# ProPrj_Flipper_Wifi_and_433MHz_shield_20.net
KiCad netlist of a schematic drawn in EasyEDA Pro
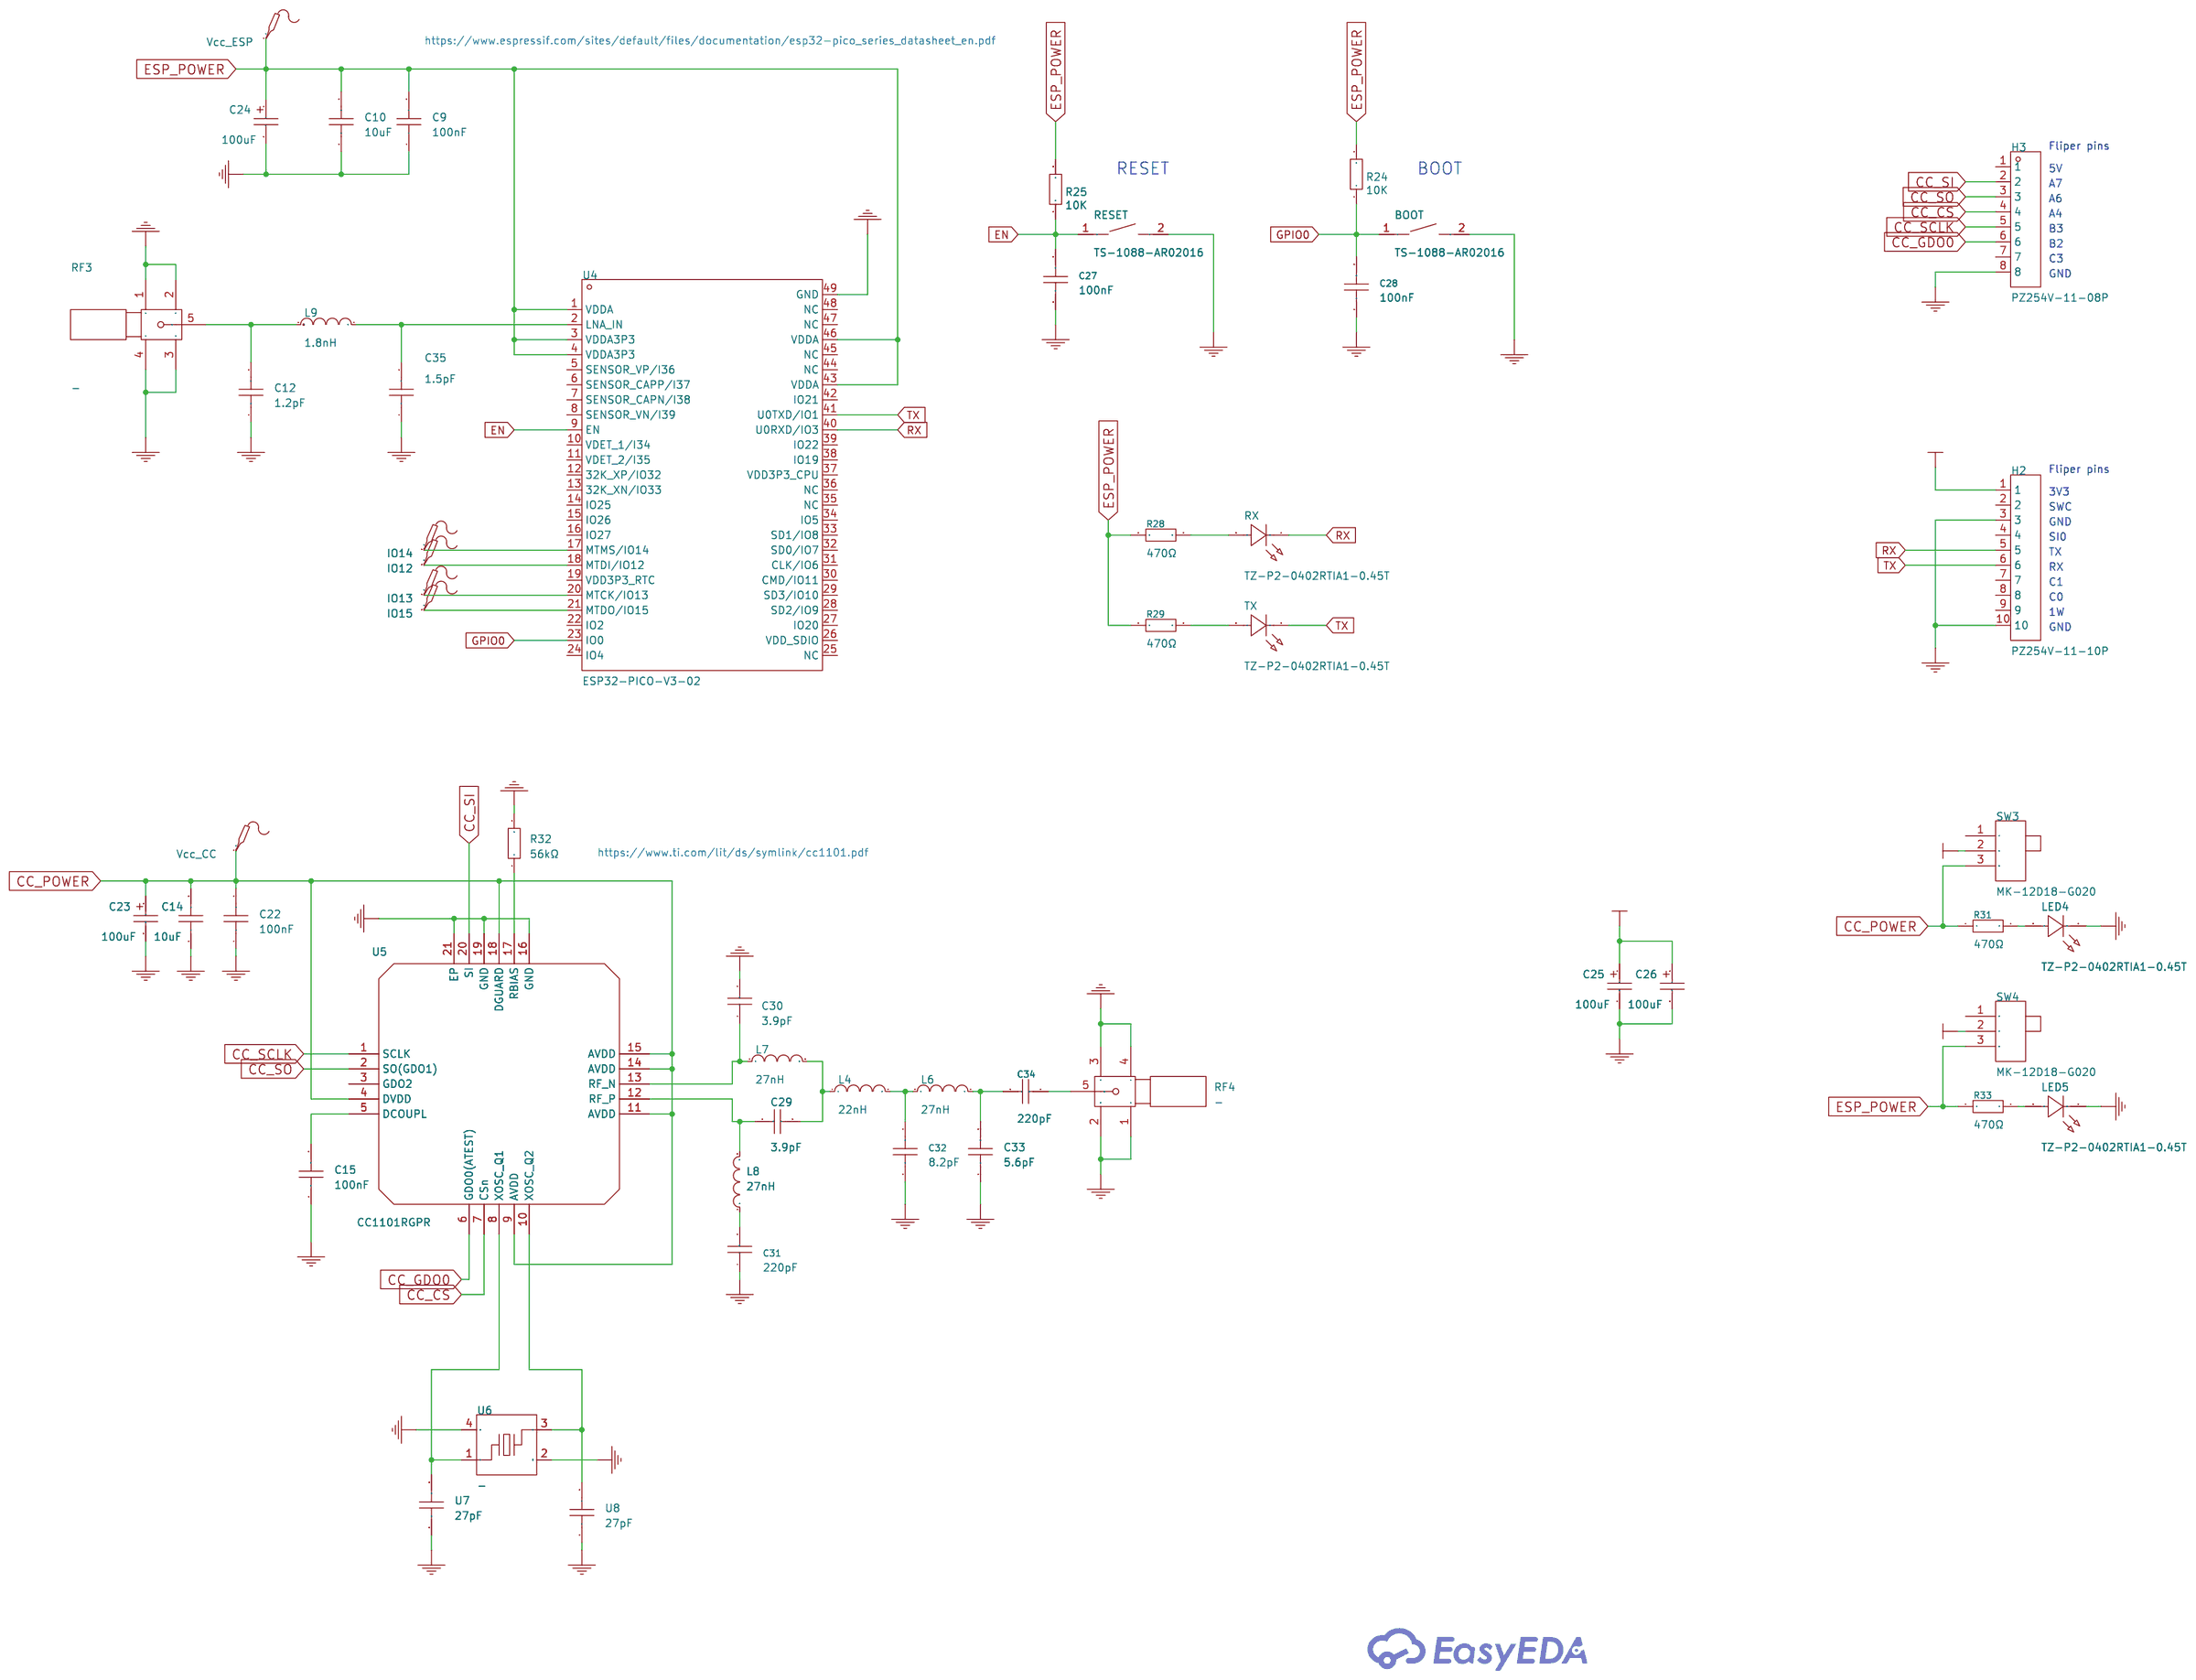
[diagram p0: schematic sheet]

(export (version "E")
  (design (tool "Eeschema 10.0.6"))
  (components
    (comp (ref "BOOT")
      (value "TS-1088-AR02016")
      (footprint "easyedapro:SW-SMD_L3.9-W3.0-P4.45")
      (fields (field (name "Manufacturer") "XUNPU(讯普)"))
      (libsource (lib "easyedapro") (part "TS-1088-AR02016"))
    )
    (comp (ref "C9")
      (value "100nF")
      (footprint "easyedapro:C0603")
      (description "Capacitance:100nF Tolerance:±10% Tolerance:±10% Voltage Rating:50V Temperature Coefficient:X7R")
      (fields
        (field (name "Manufacturer Part") "CC0603KRX7R9BB104")
        (field (name "Manufacturer") "YAGEO(国巨)")
      )
      (libsource (lib "easyedapro") (part "CC0603KRX7R9BB104"))
    )
    (comp (ref "C10")
      (value "10uF")
      (footprint "easyedapro:C0603")
      (fields
        (field (name "Manufacturer Part") "CL10A106MP8NNNC")
        (field (name "Manufacturer") "SAMSUNG(三星)")
      )
      (libsource (lib "easyedapro") (part "CL10A106MP8NNNC"))
    )
    (comp (ref "C12")
      (value "1.2pF")
      (footprint "easyedapro:C0201")
      (fields
        (field (name "Manufacturer Part") "GRM0335C1H1R2BA01D")
        (field (name "Manufacturer") "muRata(村田)")
      )
      (libsource (lib "easyedapro") (part "GRM0335C1H1R2BA01D"))
    )
    (comp (ref "C14")
      (value "10uF")
      (footprint "easyedapro:C0603")
      (fields
        (field (name "Manufacturer Part") "CL10A106MP8NNNC")
        (field (name "Manufacturer") "SAMSUNG(三星)")
      )
      (libsource (lib "easyedapro") (part "CL10A106MP8NNNC"))
    )
    (comp (ref "C15")
      (value "100nF")
      (footprint "easyedapro:C0603")
      (description "Capacitance:100nF Tolerance:±10% Tolerance:±10% Voltage Rating:50V Temperature Coefficient:X7R")
      (fields
        (field (name "Manufacturer Part") "CC0603KRX7R9BB104")
        (field (name "Manufacturer") "YAGEO(国巨)")
      )
      (libsource (lib "easyedapro") (part "CC0603KRX7R9BB104"))
    )
    (comp (ref "C22")
      (value "100nF")
      (footprint "easyedapro:C0603")
      (description "Capacitance:100nF Tolerance:±10% Tolerance:±10% Voltage Rating:50V Temperature Coefficient:X7R")
      (fields
        (field (name "Manufacturer Part") "CC0603KRX7R9BB104")
        (field (name "Manufacturer") "YAGEO(国巨)")
      )
      (libsource (lib "easyedapro") (part "CC0603KRX7R9BB104"))
    )
    (comp (ref "C23")
      (value "100uF")
      (footprint "easyedapro:CASE-B_3528")
      (fields (field (name "Manufacturer Part") "TAJB107K006RNJ") (field (name "Manufacturer") "Kyocera AVX"))
      (libsource (lib "easyedapro") (part "TAJB107K006RNJ"))
    )
    (comp (ref "C24")
      (value "100uF")
      (footprint "easyedapro:CASE-B_3528")
      (fields (field (name "Manufacturer Part") "TAJB107K006RNJ") (field (name "Manufacturer") "Kyocera AVX"))
      (libsource (lib "easyedapro") (part "TAJB107K006RNJ"))
    )
    (comp (ref "C25")
      (value "100uF")
      (footprint "easyedapro:CASE-B_3528")
      (fields (field (name "Manufacturer Part") "TAJB107K006RNJ") (field (name "Manufacturer") "Kyocera AVX"))
      (libsource (lib "easyedapro") (part "TAJB107K006RNJ"))
    )
    (comp (ref "C26")
      (value "100uF")
      (footprint "easyedapro:CASE-B_3528")
      (fields (field (name "Manufacturer Part") "TAJB107K006RNJ") (field (name "Manufacturer") "Kyocera AVX"))
      (libsource (lib "easyedapro") (part "TAJB107K006RNJ"))
    )
    (comp (ref "C27")
      (value "100nF")
      (footprint "easyedapro:C0402")
      (fields
        (field (name "Manufacturer Part") "CC0402KRX7R7BB104")
        (field (name "Manufacturer") "YAGEO(国巨)")
      )
      (libsource (lib "easyedapro") (part "CC0402KRX7R7BB104"))
    )
    (comp (ref "C28")
      (value "100nF")
      (footprint "easyedapro:C0402")
      (fields
        (field (name "Manufacturer Part") "CC0402KRX7R7BB104")
        (field (name "Manufacturer") "YAGEO(国巨)")
      )
      (libsource (lib "easyedapro") (part "CC0402KRX7R7BB104"))
    )
    (comp (ref "C29")
      (value "3.9pF")
      (footprint "easyedapro:C0402")
      (fields (field (name "Manufacturer Part") "0402CG3R9C500NT") (field (name "Manufacturer") "FH(风华)"))
      (libsource (lib "easyedapro") (part "0402CG3R9C500NT"))
    )
    (comp (ref "C30")
      (value "3.9pF")
      (footprint "easyedapro:C0402")
      (fields (field (name "Manufacturer Part") "0402CG3R9C500NT") (field (name "Manufacturer") "FH(风华)"))
      (libsource (lib "easyedapro") (part "0402CG3R9C500NT"))
    )
    (comp (ref "C31")
      (value "220pF")
      (footprint "easyedapro:C0402")
      (description "Capacitance:220pF Tolerance:±5% Tolerance:±5% Voltage Rating:50V Temperature Coefficient:NP0")
      (fields
        (field (name "Manufacturer Part") "CC0402JRNPO9BN221")
        (field (name "Manufacturer") "YAGEO(国巨)")
      )
      (libsource (lib "easyedapro") (part "CC0402JRNPO9BN221"))
    )
    (comp (ref "C32")
      (value "8.2pF")
      (footprint "easyedapro:C0402")
      (fields
        (field (name "Manufacturer Part") "CC0402BRNPO9BN8R2")
        (field (name "Manufacturer") "YAGEO(国巨)")
      )
      (libsource (lib "easyedapro") (part "CC0402BRNPO9BN8R2"))
    )
    (comp (ref "C33")
      (value "5.6pF")
      (footprint "easyedapro:C0402")
      (fields
        (field (name "Manufacturer Part") "CC0402BRNPO9BN5R6")
        (field (name "Manufacturer") "YAGEO(国巨)")
      )
      (libsource (lib "easyedapro") (part "CC0402BRNPO9BN5R6"))
    )
    (comp (ref "C34")
      (value "220pF")
      (footprint "easyedapro:C0402")
      (description "Capacitance:220pF Tolerance:±5% Tolerance:±5% Voltage Rating:50V Temperature Coefficient:NP0")
      (fields
        (field (name "Manufacturer Part") "CC0402JRNPO9BN221")
        (field (name "Manufacturer") "YAGEO(国巨)")
      )
      (libsource (lib "easyedapro") (part "CC0402JRNPO9BN221"))
    )
    (comp (ref "C35")
      (value "1.5pF")
      (footprint "easyedapro:C0201")
      (fields
        (field (name "Manufacturer Part") "GRM0335C1H1R5BA01D")
        (field (name "Manufacturer") "muRata(村田)")
      )
      (libsource (lib "easyedapro") (part "GRM0335C1H1R5BA01D"))
    )
    (comp (ref "H2")
      (value "PZ254V-11-10P")
      (footprint "easyedapro:HDR-TH_10P-P2.54-V-M")
      (fields (field (name "Manufacturer") "XFCN(兴飞)"))
      (libsource (lib "easyedapro") (part "PZ254V-11-10P"))
    )
    (comp (ref "H3")
      (value "PZ254V-11-08P")
      (footprint "easyedapro:HDR-TH_8P-P2.54-V-M")
      (fields (field (name "Manufacturer") "XFCN(兴飞)"))
      (libsource (lib "easyedapro") (part "PZ254V-11-08P"))
    )
    (comp (ref "IO12")
      (value "~")
      (footprint "easyedapro:Test-Point-0.5mm")
      (description "Test Point 测试点")
      (libsource (lib "easyedapro") (part "Test-Point"))
    )
    (comp (ref "IO13")
      (value "~")
      (footprint "easyedapro:Test-Point-0.5mm")
      (description "Test Point 测试点")
      (libsource (lib "easyedapro") (part "Test-Point"))
    )
    (comp (ref "IO14")
      (value "~")
      (footprint "easyedapro:Test-Point-0.5mm")
      (description "Test Point 测试点")
      (libsource (lib "easyedapro") (part "Test-Point"))
    )
    (comp (ref "IO15")
      (value "~")
      (footprint "easyedapro:Test-Point-0.5mm")
      (description "Test Point 测试点")
      (libsource (lib "easyedapro") (part "Test-Point"))
    )
    (comp (ref "L4")
      (value "22nH")
      (footprint "easyedapro:L0402")
      (fields (field (name "Manufacturer Part") "LQG15HS22NJ02D") (field (name "Manufacturer") "muRata(村田)"))
      (libsource (lib "easyedapro") (part "LQG15HS22NJ02D"))
    )
    (comp (ref "L6")
      (value "27nH")
      (footprint "easyedapro:L0402-RD")
      (fields (field (name "Manufacturer Part") "LQG15HS27NJ02D") (field (name "Manufacturer") "muRata(村田)"))
      (libsource (lib "easyedapro") (part "LQG15HS27NJ02D"))
    )
    (comp (ref "L7")
      (value "27nH")
      (footprint "easyedapro:L0402-RD")
      (fields (field (name "Manufacturer Part") "LQG15HS27NJ02D") (field (name "Manufacturer") "muRata(村田)"))
      (libsource (lib "easyedapro") (part "LQG15HS27NJ02D"))
    )
    (comp (ref "L8")
      (value "27nH")
      (footprint "easyedapro:L0402-RD")
      (fields (field (name "Manufacturer Part") "LQG15HS27NJ02D") (field (name "Manufacturer") "muRata(村田)"))
      (libsource (lib "easyedapro") (part "LQG15HS27NJ02D"))
    )
    (comp (ref "L9")
      (value "1.8nH")
      (footprint "easyedapro:L0201-RD")
      (fields (field (name "Manufacturer Part") "LQP03TN1N8B02D") (field (name "Manufacturer") "muRata(村田)"))
      (libsource (lib "easyedapro") (part "LQP03TN1N8B02D"))
    )
    (comp (ref "LED4")
      (value "TZ-P2-0402RTIA1-0.45T")
      (footprint "easyedapro:LED0402-RD_RED")
      (fields (field (name "Manufacturer") "TUOZHAN(拓展光电)"))
      (libsource (lib "easyedapro") (part "TZ-P2-0402RTIA1-0.45T"))
    )
    (comp (ref "LED5")
      (value "TZ-P2-0402RTIA1-0.45T")
      (footprint "easyedapro:LED0402-RD_RED")
      (fields (field (name "Manufacturer") "TUOZHAN(拓展光电)"))
      (libsource (lib "easyedapro") (part "TZ-P2-0402RTIA1-0.45T"))
    )
    (comp (ref "R24")
      (value "10K")
      (footprint "easyedapro:R0603")
      (fields (field (name "Manufacturer Part") "RC0603DR-0710KL") (field (name "Manufacturer") "YAGEO(国巨)"))
      (libsource (lib "easyedapro") (part "10K"))
    )
    (comp (ref "R25")
      (value "10K")
      (footprint "easyedapro:R0603")
      (fields (field (name "Manufacturer Part") "RC0603DR-0710KL") (field (name "Manufacturer") "YAGEO(国巨)"))
      (libsource (lib "easyedapro") (part "10K"))
    )
    (comp (ref "R28")
      (value "470Ω")
      (footprint "easyedapro:R0402")
      (fields
        (field (name "Manufacturer Part") "0402WGF4700TCE")
        (field (name "Manufacturer") "UNI-ROYAL(厚声)")
      )
      (libsource (lib "easyedapro") (part "0402WGF4700TCE"))
    )
    (comp (ref "R29")
      (value "470Ω")
      (footprint "easyedapro:R0402")
      (fields
        (field (name "Manufacturer Part") "0402WGF4700TCE")
        (field (name "Manufacturer") "UNI-ROYAL(厚声)")
      )
      (libsource (lib "easyedapro") (part "0402WGF4700TCE"))
    )
    (comp (ref "R31")
      (value "470Ω")
      (footprint "easyedapro:R0402")
      (fields
        (field (name "Manufacturer Part") "0402WGF4700TCE")
        (field (name "Manufacturer") "UNI-ROYAL(厚声)")
      )
      (libsource (lib "easyedapro") (part "0402WGF4700TCE"))
    )
    (comp (ref "R32")
      (value "56kΩ")
      (footprint "easyedapro:R0402")
      (fields
        (field (name "Manufacturer Part") "0402WGF5602TCE")
        (field (name "Manufacturer") "UNI-ROYAL(厚声)")
      )
      (libsource (lib "easyedapro") (part "0402WGF5602TCE"))
    )
    (comp (ref "R33")
      (value "470Ω")
      (footprint "easyedapro:R0402")
      (fields
        (field (name "Manufacturer Part") "0402WGF4700TCE")
        (field (name "Manufacturer") "UNI-ROYAL(厚声)")
      )
      (libsource (lib "easyedapro") (part "0402WGF4700TCE"))
    )
    (comp (ref "RESET")
      (value "TS-1088-AR02016")
      (footprint "easyedapro:SW-SMD_L3.9-W3.0-P4.45")
      (fields (field (name "Manufacturer") "XUNPU(讯普)"))
      (libsource (lib "easyedapro") (part "TS-1088-AR02016"))
    )
    (comp (ref "RF3")
      (value "-")
      (footprint "easyedapro:SMA-SMD_BWSMA-KE-P001")
      (fields
        (field (name "Manufacturer Part") "BWSMA-KE-P001")
        (field (name "Manufacturer") "BAT WIRELESS(蝙蝠无线)")
      )
      (libsource (lib "easyedapro") (part "BWSMA-KE-P001"))
    )
    (comp (ref "RF4")
      (value "-")
      (footprint "easyedapro:SMA-SMD_BWSMA-KE-P001")
      (fields
        (field (name "Manufacturer Part") "BWSMA-KE-P001")
        (field (name "Manufacturer") "BAT WIRELESS(蝙蝠无线)")
      )
      (libsource (lib "easyedapro") (part "BWSMA-KE-P001"))
    )
    (comp (ref "RX")
      (value "TZ-P2-0402RTIA1-0.45T")
      (footprint "easyedapro:LED0402-RD_RED")
      (fields (field (name "Manufacturer") "TUOZHAN(拓展光电)"))
      (libsource (lib "easyedapro") (part "TZ-P2-0402RTIA1-0.45T"))
    )
    (comp (ref "SW3")
      (value "MK-12D18-G020")
      (footprint "easyedapro:SW-TH_MK-12D18-G040")
      (fields (field (name "Manufacturer") "G-Switch(品赞)"))
      (libsource (lib "easyedapro") (part "MK-12D18-G020"))
    )
    (comp (ref "SW4")
      (value "MK-12D18-G020")
      (footprint "easyedapro:SW-TH_MK-12D18-G040")
      (fields (field (name "Manufacturer") "G-Switch(品赞)"))
      (libsource (lib "easyedapro") (part "MK-12D18-G020"))
    )
    (comp (ref "TX")
      (value "TZ-P2-0402RTIA1-0.45T")
      (footprint "easyedapro:LED0402-RD_RED")
      (fields (field (name "Manufacturer") "TUOZHAN(拓展光电)"))
      (libsource (lib "easyedapro") (part "TZ-P2-0402RTIA1-0.45T"))
    )
    (comp (ref "U4")
      (value "ESP32-PICO-V3-02")
      (footprint "easyedapro:QFN-48_L7.0-W7.0-P0.50-BL-EP5.1")
      (fields (field (name "Manufacturer") "ESPRESSIF(乐鑫)"))
      (libsource (lib "easyedapro") (part "ESP32-PICO-V3-02"))
    )
    (comp (ref "U5")
      (value "CC1101RGPR")
      (footprint "easyedapro:QFN-20_L4.0-W4.0-P0.5-TL-EP")
      (fields (field (name "Manufacturer") "TI(德州仪器)"))
      (libsource (lib "easyedapro") (part "CC1101RGPR"))
    )
    (comp (ref "U6")
      (value "-")
      (footprint "easyedapro:CRYSTAL-SMD_4P-L2.5-W2.0-BL")
      (description "Type:- Frequency:- Load Capacitance:- Operating Temperature:- Operating Temperature:-")
      (fields
        (field (name "Manufacturer Part") "NX2520SA-27MHZ-STD-CSW-5")
        (field (name "Manufacturer") "NDK")
      )
      (libsource (lib "easyedapro") (part "NX2520SA-27MHZ-STD-CSW-5"))
    )
    (comp (ref "U7")
      (value "27pF")
      (footprint "easyedapro:C0402")
      (description "Capacitance: Tolerance:±1% Tolerance:±1% Voltage Rated:50V")
      (fields
        (field (name "Manufacturer Part") "GCM1555C1H270FA16D")
        (field (name "Manufacturer") "muRata(村田)")
      )
      (libsource (lib "easyedapro") (part "GCM1555C1H270FA16D"))
    )
    (comp (ref "U8")
      (value "27pF")
      (footprint "easyedapro:C0402")
      (description "Capacitance: Tolerance:±1% Tolerance:±1% Voltage Rated:50V")
      (fields
        (field (name "Manufacturer Part") "GCM1555C1H270FA16D")
        (field (name "Manufacturer") "muRata(村田)")
      )
      (libsource (lib "easyedapro") (part "GCM1555C1H270FA16D"))
    )
    (comp (ref "Vcc_CC")
      (value "~")
      (footprint "easyedapro:Test-Point-0.5mm")
      (description "Test Point 测试点")
      (libsource (lib "easyedapro") (part "Test-Point"))
    )
    (comp (ref "Vcc_ESP")
      (value "~")
      (footprint "easyedapro:Test-Point-0.5mm")
      (description "Test Point 测试点")
      (libsource (lib "easyedapro") (part "Test-Point"))
    )
  )
  (nets
    (net (code "1") (name "3V3") (class "Default")
      (node (ref "C25") (pin "1") (pinfunction "1_1") (pintype "input"))
      (node (ref "C26") (pin "1") (pinfunction "1_1") (pintype "input"))
      (node (ref "H2") (pin "1") (pinfunction "1_1") (pintype "unspecified"))
      (node (ref "SW3") (pin "2") (pinfunction "2_2") (pintype "unspecified"))
      (node (ref "SW4") (pin "2") (pinfunction "2_2") (pintype "unspecified"))
    )
    (net (code "2") (name "CC_CS") (class "Default")
      (node (ref "H3") (pin "4") (pinfunction "4_4") (pintype "unspecified"))
      (node (ref "U5") (pin "7") (pinfunction "CSn_7") (pintype "unspecified"))
    )
    (net (code "3") (name "CC_GDO0") (class "Default")
      (node (ref "H3") (pin "6") (pinfunction "6_6") (pintype "unspecified"))
      (node (ref "U5") (pin "6") (pinfunction "GDO0(ATEST)_6") (pintype "unspecified"))
    )
    (net (code "4") (name "CC_POWER") (class "Default")
      (node (ref "C14") (pin "2") (pinfunction "2_2") (pintype "unspecified"))
      (node (ref "C22") (pin "2") (pinfunction "2_2") (pintype "unspecified"))
      (node (ref "C23") (pin "1") (pinfunction "1_1") (pintype "input"))
      (node (ref "R31") (pin "1") (pinfunction "1_1") (pintype "input"))
      (node (ref "SW3") (pin "3") (pinfunction "3_3") (pintype "unspecified"))
      (node (ref "U5") (pin "11") (pinfunction "AVDD_11") (pintype "unspecified"))
      (node (ref "U5") (pin "14") (pinfunction "AVDD_14") (pintype "unspecified"))
      (node (ref "U5") (pin "15") (pinfunction "AVDD_15") (pintype "unspecified"))
      (node (ref "U5") (pin "18") (pinfunction "DGUARD_18") (pintype "unspecified"))
      (node (ref "U5") (pin "4") (pinfunction "DVDD_4") (pintype "unspecified"))
      (node (ref "U5") (pin "9") (pinfunction "AVDD_9") (pintype "unspecified"))
      (node (ref "Vcc_CC") (pin "1") (pinfunction "1_1") (pintype "unspecified"))
    )
    (net (code "5") (name "CC_SCLK") (class "Default")
      (node (ref "H3") (pin "5") (pinfunction "5_5") (pintype "unspecified"))
      (node (ref "U5") (pin "1") (pinfunction "SCLK_1") (pintype "unspecified"))
    )
    (net (code "6") (name "CC_SI") (class "Default")
      (node (ref "H3") (pin "2") (pinfunction "2_2") (pintype "unspecified"))
      (node (ref "U5") (pin "20") (pinfunction "SI_20") (pintype "unspecified"))
    )
    (net (code "7") (name "CC_SO") (class "Default")
      (node (ref "H3") (pin "3") (pinfunction "3_3") (pintype "unspecified"))
      (node (ref "U5") (pin "2") (pinfunction "SO(GDO1)_2") (pintype "unspecified"))
    )
    (net (code "8") (name "EN") (class "Default")
      (node (ref "C27") (pin "2") (pinfunction "2_2") (pintype "input"))
      (node (ref "R25") (pin "1") (pinfunction "1_1") (pintype "input"))
      (node (ref "RESET") (pin "1") (pinfunction "1_1") (pintype "unspecified"))
      (node (ref "U4") (pin "9") (pinfunction "EN_9") (pintype "unspecified"))
    )
    (net (code "9") (name "ESP_POWER") (class "Default")
      (node (ref "C10") (pin "2") (pinfunction "2_2") (pintype "unspecified"))
      (node (ref "C24") (pin "1") (pinfunction "1_1") (pintype "input"))
      (node (ref "C9") (pin "2") (pinfunction "2_2") (pintype "unspecified"))
      (node (ref "R24") (pin "2") (pinfunction "2_2") (pintype "input"))
      (node (ref "R25") (pin "2") (pinfunction "2_2") (pintype "input"))
      (node (ref "R28") (pin "1") (pinfunction "1_1") (pintype "input"))
      (node (ref "R29") (pin "1") (pinfunction "1_1") (pintype "input"))
      (node (ref "R33") (pin "1") (pinfunction "1_1") (pintype "input"))
      (node (ref "SW4") (pin "3") (pinfunction "3_3") (pintype "unspecified"))
      (node (ref "U4") (pin "1") (pinfunction "VDDA_1") (pintype "unspecified"))
      (node (ref "U4") (pin "3") (pinfunction "VDDA3P3_3") (pintype "unspecified"))
      (node (ref "U4") (pin "4") (pinfunction "VDDA3P3_4") (pintype "unspecified"))
      (node (ref "U4") (pin "43") (pinfunction "VDDA_43") (pintype "unspecified"))
      (node (ref "U4") (pin "46") (pinfunction "VDDA_46") (pintype "unspecified"))
      (node (ref "Vcc_ESP") (pin "1") (pinfunction "1_1") (pintype "unspecified"))
    )
    (net (code "10") (name "GND") (class "Default")
      (node (ref "BOOT") (pin "2") (pinfunction "2_2") (pintype "unspecified"))
      (node (ref "C10") (pin "1") (pinfunction "1_1") (pintype "unspecified"))
      (node (ref "C12") (pin "1") (pinfunction "1_1") (pintype "unspecified"))
      (node (ref "C14") (pin "1") (pinfunction "1_1") (pintype "unspecified"))
      (node (ref "C15") (pin "1") (pinfunction "1_1") (pintype "unspecified"))
      (node (ref "C22") (pin "1") (pinfunction "1_1") (pintype "unspecified"))
      (node (ref "C23") (pin "2") (pinfunction "2_2") (pintype "input"))
      (node (ref "C24") (pin "2") (pinfunction "2_2") (pintype "input"))
      (node (ref "C25") (pin "2") (pinfunction "2_2") (pintype "input"))
      (node (ref "C26") (pin "2") (pinfunction "2_2") (pintype "input"))
      (node (ref "C27") (pin "1") (pinfunction "1_1") (pintype "input"))
      (node (ref "C28") (pin "1") (pinfunction "1_1") (pintype "input"))
      (node (ref "C30") (pin "2") (pinfunction "2_2") (pintype "input"))
      (node (ref "C31") (pin "1") (pinfunction "1_1") (pintype "input"))
      (node (ref "C32") (pin "2") (pinfunction "2_2") (pintype "input"))
      (node (ref "C33") (pin "1") (pinfunction "1_1") (pintype "unspecified"))
      (node (ref "C35") (pin "1") (pinfunction "1_1") (pintype "unspecified"))
      (node (ref "C9") (pin "1") (pinfunction "1_1") (pintype "unspecified"))
      (node (ref "H2") (pin "10") (pinfunction "10_10") (pintype "unspecified"))
      (node (ref "H2") (pin "3") (pinfunction "3_3") (pintype "unspecified"))
      (node (ref "H3") (pin "8") (pinfunction "8_8") (pintype "unspecified"))
      (node (ref "LED4") (pin "1") (pinfunction "K_1") (pintype "unspecified"))
      (node (ref "LED5") (pin "1") (pinfunction "K_1") (pintype "unspecified"))
      (node (ref "R32") (pin "2") (pinfunction "2_2") (pintype "input"))
      (node (ref "RESET") (pin "2") (pinfunction "2_2") (pintype "unspecified"))
      (node (ref "RF3") (pin "1") (pinfunction "1_1") (pintype "unspecified"))
      (node (ref "RF3") (pin "2") (pinfunction "2_2") (pintype "unspecified"))
      (node (ref "RF3") (pin "3") (pinfunction "3_3") (pintype "unspecified"))
      (node (ref "RF3") (pin "4") (pinfunction "4_4") (pintype "unspecified"))
      (node (ref "RF4") (pin "1") (pinfunction "1_1") (pintype "unspecified"))
      (node (ref "RF4") (pin "2") (pinfunction "2_2") (pintype "unspecified"))
      (node (ref "RF4") (pin "3") (pinfunction "3_3") (pintype "unspecified"))
      (node (ref "RF4") (pin "4") (pinfunction "4_4") (pintype "unspecified"))
      (node (ref "U4") (pin "49") (pinfunction "GND_49") (pintype "unspecified"))
      (node (ref "U5") (pin "16") (pinfunction "GND_16") (pintype "unspecified"))
      (node (ref "U5") (pin "19") (pinfunction "GND_19") (pintype "unspecified"))
      (node (ref "U5") (pin "21") (pinfunction "EP_21") (pintype "unspecified"))
      (node (ref "U6") (pin "2") (pinfunction "GND_2") (pintype "input"))
      (node (ref "U6") (pin "4") (pinfunction "GND_4") (pintype "input"))
      (node (ref "U7") (pin "1") (pinfunction "1_1") (pintype "unspecified"))
      (node (ref "U8") (pin "1") (pinfunction "1_1") (pintype "unspecified"))
    )
    (net (code "11") (name "GPIO0") (class "Default")
      (node (ref "BOOT") (pin "1") (pinfunction "1_1") (pintype "unspecified"))
      (node (ref "C28") (pin "2") (pinfunction "2_2") (pintype "input"))
      (node (ref "R24") (pin "1") (pinfunction "1_1") (pintype "input"))
      (node (ref "U4") (pin "23") (pinfunction "IO0_23") (pintype "unspecified"))
    )
    (net (code "12") (name "Net-(C12-Pad2)") (class "Default")
      (node (ref "C12") (pin "2") (pinfunction "2_2") (pintype "unspecified"))
      (node (ref "L9") (pin "1") (pinfunction "1_1") (pintype "input"))
      (node (ref "RF3") (pin "5") (pinfunction "5_5") (pintype "unspecified"))
    )
    (net (code "13") (name "Net-(C29-Pad2)") (class "Default")
      (node (ref "C29") (pin "2") (pinfunction "2_2") (pintype "input"))
      (node (ref "L4") (pin "1") (pinfunction "1_1") (pintype "unspecified"))
      (node (ref "L7") (pin "2") (pinfunction "2_2") (pintype "unspecified"))
    )
    (net (code "14") (name "Net-(C31-Pad2)") (class "Default")
      (node (ref "C31") (pin "2") (pinfunction "2_2") (pintype "input"))
      (node (ref "L8") (pin "1") (pinfunction "1_1") (pintype "unspecified"))
    )
    (net (code "15") (name "Net-(C32-Pad1)") (class "Default")
      (node (ref "C32") (pin "1") (pinfunction "1_1") (pintype "input"))
      (node (ref "L4") (pin "2") (pinfunction "2_2") (pintype "unspecified"))
      (node (ref "L6") (pin "1") (pinfunction "1_1") (pintype "unspecified"))
    )
    (net (code "16") (name "Net-(C33-Pad2)") (class "Default")
      (node (ref "C33") (pin "2") (pinfunction "2_2") (pintype "unspecified"))
      (node (ref "C34") (pin "2") (pinfunction "2_2") (pintype "input"))
      (node (ref "L6") (pin "2") (pinfunction "2_2") (pintype "unspecified"))
    )
    (net (code "17") (name "Net-(C34-Pad1)") (class "Default")
      (node (ref "C34") (pin "1") (pinfunction "1_1") (pintype "input"))
      (node (ref "RF4") (pin "5") (pinfunction "5_5") (pintype "unspecified"))
    )
    (net (code "18") (name "Net-(LED4-A)") (class "Default")
      (node (ref "LED4") (pin "2") (pinfunction "A_2") (pintype "unspecified"))
      (node (ref "R31") (pin "2") (pinfunction "2_2") (pintype "input"))
    )
    (net (code "19") (name "Net-(LED5-A)") (class "Default")
      (node (ref "LED5") (pin "2") (pinfunction "A_2") (pintype "unspecified"))
      (node (ref "R33") (pin "2") (pinfunction "2_2") (pintype "input"))
    )
    (net (code "20") (name "Net-(RX-A)") (class "Default")
      (node (ref "R28") (pin "2") (pinfunction "2_2") (pintype "input"))
      (node (ref "RX") (pin "2") (pinfunction "A_2") (pintype "unspecified"))
    )
    (net (code "21") (name "Net-(TX-A)") (class "Default")
      (node (ref "R29") (pin "2") (pinfunction "2_2") (pintype "input"))
      (node (ref "TX") (pin "2") (pinfunction "A_2") (pintype "unspecified"))
    )
    (net (code "22") (name "Net-(U4-LNA_IN)") (class "Default")
      (node (ref "C35") (pin "2") (pinfunction "2_2") (pintype "unspecified"))
      (node (ref "L9") (pin "2") (pinfunction "2_2") (pintype "input"))
      (node (ref "U4") (pin "2") (pinfunction "LNA_IN_2") (pintype "unspecified"))
    )
    (net (code "23") (name "Net-(U4-MTCK{slash}IO13)") (class "Default")
      (node (ref "IO13") (pin "1") (pinfunction "1_1") (pintype "unspecified"))
      (node (ref "U4") (pin "20") (pinfunction "MTCK/IO13_20") (pintype "unspecified"))
    )
    (net (code "24") (name "Net-(U4-MTDI{slash}IO12)") (class "Default")
      (node (ref "IO12") (pin "1") (pinfunction "1_1") (pintype "unspecified"))
      (node (ref "U4") (pin "18") (pinfunction "MTDI/IO12_18") (pintype "unspecified"))
    )
    (net (code "25") (name "Net-(U4-MTDO{slash}IO15)") (class "Default")
      (node (ref "IO15") (pin "1") (pinfunction "1_1") (pintype "unspecified"))
      (node (ref "U4") (pin "21") (pinfunction "MTDO/IO15_21") (pintype "unspecified"))
    )
    (net (code "26") (name "Net-(U4-MTMS{slash}IO14)") (class "Default")
      (node (ref "IO14") (pin "1") (pinfunction "1_1") (pintype "unspecified"))
      (node (ref "U4") (pin "17") (pinfunction "MTMS/IO14_17") (pintype "unspecified"))
    )
    (net (code "27") (name "Net-(U5-DCOUPL)") (class "Default")
      (node (ref "C15") (pin "2") (pinfunction "2_2") (pintype "unspecified"))
      (node (ref "U5") (pin "5") (pinfunction "DCOUPL_5") (pintype "unspecified"))
    )
    (net (code "28") (name "Net-(U5-RBIAS)") (class "Default")
      (node (ref "R32") (pin "1") (pinfunction "1_1") (pintype "input"))
      (node (ref "U5") (pin "17") (pinfunction "RBIAS_17") (pintype "unspecified"))
    )
    (net (code "29") (name "Net-(U5-RF_N)") (class "Default")
      (node (ref "C30") (pin "1") (pinfunction "1_1") (pintype "input"))
      (node (ref "L7") (pin "1") (pinfunction "1_1") (pintype "unspecified"))
      (node (ref "U5") (pin "13") (pinfunction "RF_N_13") (pintype "unspecified"))
    )
    (net (code "30") (name "Net-(U5-RF_P)") (class "Default")
      (node (ref "C29") (pin "1") (pinfunction "1_1") (pintype "input"))
      (node (ref "L8") (pin "2") (pinfunction "2_2") (pintype "unspecified"))
      (node (ref "U5") (pin "12") (pinfunction "RF_P_12") (pintype "unspecified"))
    )
    (net (code "31") (name "Net-(U5-XOSC_Q1)") (class "Default")
      (node (ref "U5") (pin "8") (pinfunction "XOSC_Q1_8") (pintype "unspecified"))
      (node (ref "U6") (pin "1") (pinfunction "1_1") (pintype "input"))
      (node (ref "U7") (pin "2") (pinfunction "2_2") (pintype "unspecified"))
    )
    (net (code "32") (name "Net-(U5-XOSC_Q2)") (class "Default")
      (node (ref "U5") (pin "10") (pinfunction "XOSC_Q2_10") (pintype "unspecified"))
      (node (ref "U6") (pin "3") (pinfunction "3_3") (pintype "input"))
      (node (ref "U8") (pin "2") (pinfunction "2_2") (pintype "unspecified"))
    )
    (net (code "33") (name "RX") (class "Default")
      (node (ref "H2") (pin "5") (pinfunction "5_5") (pintype "unspecified"))
      (node (ref "RX") (pin "1") (pinfunction "K_1") (pintype "unspecified"))
      (node (ref "U4") (pin "40") (pinfunction "U0RXD/IO3_40") (pintype "unspecified"))
    )
    (net (code "34") (name "TX") (class "Default")
      (node (ref "H2") (pin "6") (pinfunction "6_6") (pintype "unspecified"))
      (node (ref "TX") (pin "1") (pinfunction "K_1") (pintype "unspecified"))
      (node (ref "U4") (pin "41") (pinfunction "U0TXD/IO1_41") (pintype "unspecified"))
    )
    (net (code "35") (name "unconnected-(H2-Pad2)") (class "Default")
      (node (ref "H2") (pin "2") (pinfunction "2_2") (pintype "unspecified"))
    )
    (net (code "36") (name "unconnected-(H2-Pad4)") (class "Default")
      (node (ref "H2") (pin "4") (pinfunction "4_4") (pintype "unspecified"))
    )
    (net (code "37") (name "unconnected-(H2-Pad7)") (class "Default")
      (node (ref "H2") (pin "7") (pinfunction "7_7") (pintype "unspecified"))
    )
    (net (code "38") (name "unconnected-(H2-Pad8)") (class "Default")
      (node (ref "H2") (pin "8") (pinfunction "8_8") (pintype "unspecified"))
    )
    (net (code "39") (name "unconnected-(H2-Pad9)") (class "Default")
      (node (ref "H2") (pin "9") (pinfunction "9_9") (pintype "unspecified"))
    )
    (net (code "40") (name "unconnected-(H3-Pad1)") (class "Default")
      (node (ref "H3") (pin "1") (pinfunction "1_1") (pintype "unspecified"))
    )
    (net (code "41") (name "unconnected-(H3-Pad7)") (class "Default")
      (node (ref "H3") (pin "7") (pinfunction "7_7") (pintype "unspecified"))
    )
    (net (code "42") (name "unconnected-(SW3-Pad1)") (class "Default")
      (node (ref "SW3") (pin "1") (pinfunction "1_1") (pintype "unspecified"))
    )
    (net (code "43") (name "unconnected-(SW4-Pad1)") (class "Default")
      (node (ref "SW4") (pin "1") (pinfunction "1_1") (pintype "unspecified"))
    )
    (net (code "44") (name "unconnected-(U4-32K_XN{slash}IO33-Pad13)") (class "Default")
      (node (ref "U4") (pin "13") (pinfunction "32K_XN/IO33_13") (pintype "unspecified"))
    )
    (net (code "45") (name "unconnected-(U4-32K_XP{slash}IO32-Pad12)") (class "Default")
      (node (ref "U4") (pin "12") (pinfunction "32K_XP/IO32_12") (pintype "unspecified"))
    )
    (net (code "46") (name "unconnected-(U4-CLK{slash}IO6-Pad31)") (class "Default")
      (node (ref "U4") (pin "31") (pinfunction "CLK/IO6_31") (pintype "unspecified"))
    )
    (net (code "47") (name "unconnected-(U4-CMD{slash}IO11-Pad30)") (class "Default")
      (node (ref "U4") (pin "30") (pinfunction "CMD/IO11_30") (pintype "unspecified"))
    )
    (net (code "48") (name "unconnected-(U4-IO2-Pad22)") (class "Default")
      (node (ref "U4") (pin "22") (pinfunction "IO2_22") (pintype "unspecified"))
    )
    (net (code "49") (name "unconnected-(U4-IO4-Pad24)") (class "Default")
      (node (ref "U4") (pin "24") (pinfunction "IO4_24") (pintype "unspecified"))
    )
    (net (code "50") (name "unconnected-(U4-IO5-Pad34)") (class "Default")
      (node (ref "U4") (pin "34") (pinfunction "IO5_34") (pintype "unspecified"))
    )
    (net (code "51") (name "unconnected-(U4-IO19-Pad38)") (class "Default")
      (node (ref "U4") (pin "38") (pinfunction "IO19_38") (pintype "unspecified"))
    )
    (net (code "52") (name "unconnected-(U4-IO20-Pad27)") (class "Default")
      (node (ref "U4") (pin "27") (pinfunction "IO20_27") (pintype "unspecified"))
    )
    (net (code "53") (name "unconnected-(U4-IO21-Pad42)") (class "Default")
      (node (ref "U4") (pin "42") (pinfunction "IO21_42") (pintype "unspecified"))
    )
    (net (code "54") (name "unconnected-(U4-IO22-Pad39)") (class "Default")
      (node (ref "U4") (pin "39") (pinfunction "IO22_39") (pintype "unspecified"))
    )
    (net (code "55") (name "unconnected-(U4-IO25-Pad14)") (class "Default")
      (node (ref "U4") (pin "14") (pinfunction "IO25_14") (pintype "unspecified"))
    )
    (net (code "56") (name "unconnected-(U4-IO26-Pad15)") (class "Default")
      (node (ref "U4") (pin "15") (pinfunction "IO26_15") (pintype "unspecified"))
    )
    (net (code "57") (name "unconnected-(U4-IO27-Pad16)") (class "Default")
      (node (ref "U4") (pin "16") (pinfunction "IO27_16") (pintype "unspecified"))
    )
    (net (code "58") (name "unconnected-(U4-NC-Pad25)") (class "Default")
      (node (ref "U4") (pin "25") (pinfunction "NC_25") (pintype "unspecified"))
    )
    (net (code "59") (name "unconnected-(U4-NC-Pad35)") (class "Default")
      (node (ref "U4") (pin "35") (pinfunction "NC_35") (pintype "unspecified"))
    )
    (net (code "60") (name "unconnected-(U4-NC-Pad36)") (class "Default")
      (node (ref "U4") (pin "36") (pinfunction "NC_36") (pintype "unspecified"))
    )
    (net (code "61") (name "unconnected-(U4-NC-Pad44)") (class "Default")
      (node (ref "U4") (pin "44") (pinfunction "NC_44") (pintype "unspecified"))
    )
    (net (code "62") (name "unconnected-(U4-NC-Pad45)") (class "Default")
      (node (ref "U4") (pin "45") (pinfunction "NC_45") (pintype "unspecified"))
    )
    (net (code "63") (name "unconnected-(U4-NC-Pad47)") (class "Default")
      (node (ref "U4") (pin "47") (pinfunction "NC_47") (pintype "unspecified"))
    )
    (net (code "64") (name "unconnected-(U4-NC-Pad48)") (class "Default")
      (node (ref "U4") (pin "48") (pinfunction "NC_48") (pintype "unspecified"))
    )
    (net (code "65") (name "unconnected-(U4-SD0{slash}IO7-Pad32)") (class "Default")
      (node (ref "U4") (pin "32") (pinfunction "SD0/IO7_32") (pintype "unspecified"))
    )
    (net (code "66") (name "unconnected-(U4-SD1{slash}IO8-Pad33)") (class "Default")
      (node (ref "U4") (pin "33") (pinfunction "SD1/IO8_33") (pintype "unspecified"))
    )
    (net (code "67") (name "unconnected-(U4-SD2{slash}IO9-Pad28)") (class "Default")
      (node (ref "U4") (pin "28") (pinfunction "SD2/IO9_28") (pintype "unspecified"))
    )
    (net (code "68") (name "unconnected-(U4-SD3{slash}IO10-Pad29)") (class "Default")
      (node (ref "U4") (pin "29") (pinfunction "SD3/IO10_29") (pintype "unspecified"))
    )
    (net (code "69") (name "unconnected-(U4-SENSOR_CAPN{slash}I38-Pad7)") (class "Default")
      (node (ref "U4") (pin "7") (pinfunction "SENSOR_CAPN/I38_7") (pintype "unspecified"))
    )
    (net (code "70") (name "unconnected-(U4-SENSOR_CAPP{slash}I37-Pad6)") (class "Default")
      (node (ref "U4") (pin "6") (pinfunction "SENSOR_CAPP/I37_6") (pintype "unspecified"))
    )
    (net (code "71") (name "unconnected-(U4-SENSOR_VN{slash}I39-Pad8)") (class "Default")
      (node (ref "U4") (pin "8") (pinfunction "SENSOR_VN/I39_8") (pintype "unspecified"))
    )
    (net (code "72") (name "unconnected-(U4-SENSOR_VP{slash}I36-Pad5)") (class "Default")
      (node (ref "U4") (pin "5") (pinfunction "SENSOR_VP/I36_5") (pintype "unspecified"))
    )
    (net (code "73") (name "unconnected-(U4-VDD3P3_CPU-Pad37)") (class "Default")
      (node (ref "U4") (pin "37") (pinfunction "VDD3P3_CPU_37") (pintype "unspecified"))
    )
    (net (code "74") (name "unconnected-(U4-VDD3P3_RTC-Pad19)") (class "Default")
      (node (ref "U4") (pin "19") (pinfunction "VDD3P3_RTC_19") (pintype "unspecified"))
    )
    (net (code "75") (name "unconnected-(U4-VDD_SDIO-Pad26)") (class "Default")
      (node (ref "U4") (pin "26") (pinfunction "VDD_SDIO_26") (pintype "unspecified"))
    )
    (net (code "76") (name "unconnected-(U4-VDET_1{slash}I34-Pad10)") (class "Default")
      (node (ref "U4") (pin "10") (pinfunction "VDET_1/I34_10") (pintype "unspecified"))
    )
    (net (code "77") (name "unconnected-(U4-VDET_2{slash}I35-Pad11)") (class "Default")
      (node (ref "U4") (pin "11") (pinfunction "VDET_2/I35_11") (pintype "unspecified"))
    )
    (net (code "78") (name "unconnected-(U5-GDO2-Pad3)") (class "Default")
      (node (ref "U5") (pin "3") (pinfunction "GDO2_3") (pintype "unspecified"))
    )
  )
)
